# retainer.net
KiCad netlist of a schematic drawn in EAGLE
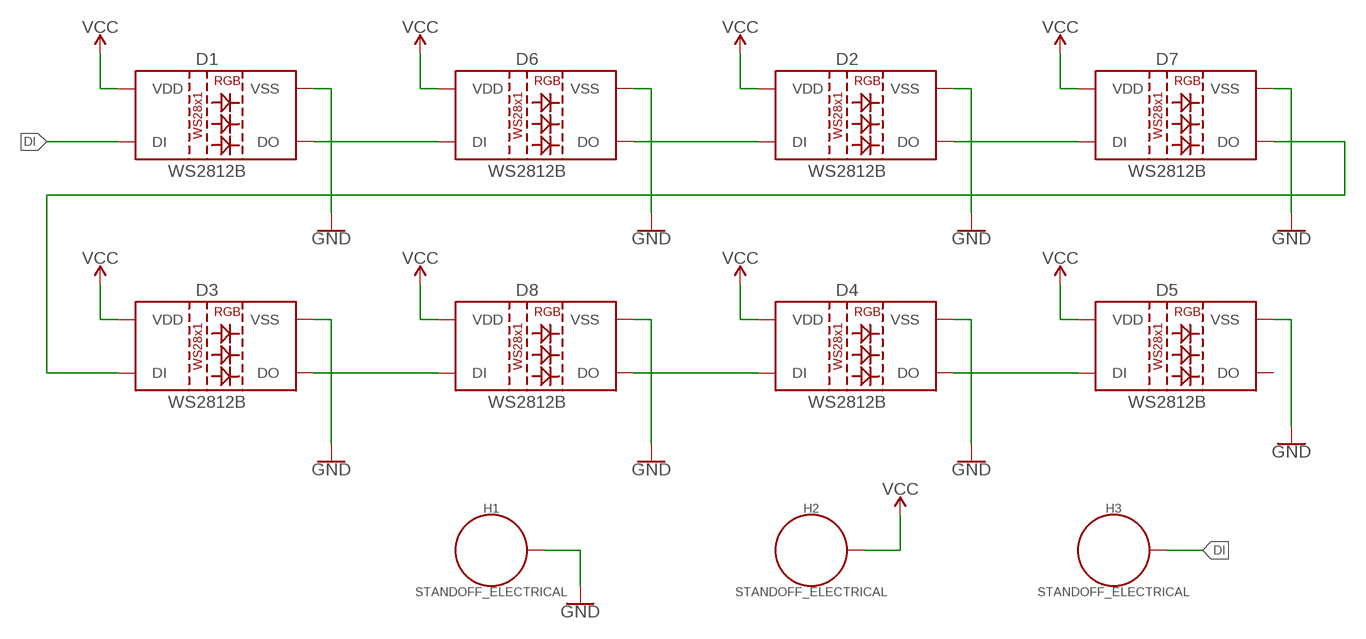
[diagram p0: schematic, sheet 1]

(export (version "E")
  (design (tool "Eeschema 10.0.6"))
  (components
    (comp (ref "D1")
      (value "WS2812B")
      (footprint "eagle-import:WS2812B")
      (libsource (lib "eagle-import") (part "WS2812B"))
    )
    (comp (ref "D2")
      (value "WS2812B")
      (footprint "eagle-import:WS2812B")
      (libsource (lib "eagle-import") (part "WS2812B"))
    )
    (comp (ref "D3")
      (value "WS2812B")
      (footprint "eagle-import:WS2812B")
      (libsource (lib "eagle-import") (part "WS2812B"))
    )
    (comp (ref "D4")
      (value "WS2812B")
      (footprint "eagle-import:WS2812B")
      (libsource (lib "eagle-import") (part "WS2812B"))
    )
    (comp (ref "D5")
      (value "WS2812B")
      (footprint "eagle-import:WS2812B")
      (libsource (lib "eagle-import") (part "WS2812B"))
    )
    (comp (ref "D6")
      (value "WS2812B")
      (footprint "eagle-import:WS2812B")
      (libsource (lib "eagle-import") (part "WS2812B"))
    )
    (comp (ref "D7")
      (value "WS2812B")
      (footprint "eagle-import:WS2812B")
      (libsource (lib "eagle-import") (part "WS2812B"))
    )
    (comp (ref "D8")
      (value "WS2812B")
      (footprint "eagle-import:WS2812B")
      (libsource (lib "eagle-import") (part "WS2812B"))
    )
    (comp (ref "H1")
      (value "STANDOFF_ELECTRICAL")
      (footprint "eagle-import:STANDOFF-ELECTRICAL")
      (libsource (lib "eagle-import") (part "STANDOFF_ELECTRICAL"))
    )
    (comp (ref "H2")
      (value "STANDOFF_ELECTRICAL")
      (footprint "eagle-import:STANDOFF-ELECTRICAL")
      (libsource (lib "eagle-import") (part "STANDOFF_ELECTRICAL"))
    )
    (comp (ref "H3")
      (value "STANDOFF_ELECTRICAL")
      (footprint "eagle-import:STANDOFF-ELECTRICAL")
      (libsource (lib "eagle-import") (part "STANDOFF_ELECTRICAL"))
    )
  )
  (nets
    (net (code "1") (name "DI") (class "Default")
      (node (ref "D1") (pin "4") (pinfunction "DI_4") (pintype "bidirectional"))
      (node (ref "H3") (pin "P1") (pinfunction "P$1_P1") (pintype "bidirectional"))
    )
    (net (code "2") (name "GND") (class "Default")
      (node (ref "D1") (pin "3") (pinfunction "VSS_3") (pintype "bidirectional"))
      (node (ref "D2") (pin "3") (pinfunction "VSS_3") (pintype "bidirectional"))
      (node (ref "D3") (pin "3") (pinfunction "VSS_3") (pintype "bidirectional"))
      (node (ref "D4") (pin "3") (pinfunction "VSS_3") (pintype "bidirectional"))
      (node (ref "D5") (pin "3") (pinfunction "VSS_3") (pintype "bidirectional"))
      (node (ref "D6") (pin "3") (pinfunction "VSS_3") (pintype "bidirectional"))
      (node (ref "D7") (pin "3") (pinfunction "VSS_3") (pintype "bidirectional"))
      (node (ref "D8") (pin "3") (pinfunction "VSS_3") (pintype "bidirectional"))
      (node (ref "H1") (pin "P1") (pinfunction "P$1_P1") (pintype "bidirectional"))
    )
    (net (code "3") (name "Net-(D1-DO)") (class "Default")
      (node (ref "D1") (pin "2") (pinfunction "DO_2") (pintype "bidirectional"))
      (node (ref "D6") (pin "4") (pinfunction "DI_4") (pintype "bidirectional"))
    )
    (net (code "4") (name "Net-(D2-DI)") (class "Default")
      (node (ref "D2") (pin "4") (pinfunction "DI_4") (pintype "bidirectional"))
      (node (ref "D6") (pin "2") (pinfunction "DO_2") (pintype "bidirectional"))
    )
    (net (code "5") (name "Net-(D2-DO)") (class "Default")
      (node (ref "D2") (pin "2") (pinfunction "DO_2") (pintype "bidirectional"))
      (node (ref "D7") (pin "4") (pinfunction "DI_4") (pintype "bidirectional"))
    )
    (net (code "6") (name "Net-(D3-DI)") (class "Default")
      (node (ref "D3") (pin "4") (pinfunction "DI_4") (pintype "bidirectional"))
      (node (ref "D7") (pin "2") (pinfunction "DO_2") (pintype "bidirectional"))
    )
    (net (code "7") (name "Net-(D3-DO)") (class "Default")
      (node (ref "D3") (pin "2") (pinfunction "DO_2") (pintype "bidirectional"))
      (node (ref "D8") (pin "4") (pinfunction "DI_4") (pintype "bidirectional"))
    )
    (net (code "8") (name "Net-(D4-DI)") (class "Default")
      (node (ref "D4") (pin "4") (pinfunction "DI_4") (pintype "bidirectional"))
      (node (ref "D8") (pin "2") (pinfunction "DO_2") (pintype "bidirectional"))
    )
    (net (code "9") (name "Net-(D4-DO)") (class "Default")
      (node (ref "D4") (pin "2") (pinfunction "DO_2") (pintype "bidirectional"))
      (node (ref "D5") (pin "4") (pinfunction "DI_4") (pintype "bidirectional"))
    )
    (net (code "10") (name "VCC") (class "Default")
      (node (ref "D1") (pin "1") (pinfunction "VDD_1") (pintype "bidirectional"))
      (node (ref "D2") (pin "1") (pinfunction "VDD_1") (pintype "bidirectional"))
      (node (ref "D3") (pin "1") (pinfunction "VDD_1") (pintype "bidirectional"))
      (node (ref "D4") (pin "1") (pinfunction "VDD_1") (pintype "bidirectional"))
      (node (ref "D5") (pin "1") (pinfunction "VDD_1") (pintype "bidirectional"))
      (node (ref "D6") (pin "1") (pinfunction "VDD_1") (pintype "bidirectional"))
      (node (ref "D7") (pin "1") (pinfunction "VDD_1") (pintype "bidirectional"))
      (node (ref "D8") (pin "1") (pinfunction "VDD_1") (pintype "bidirectional"))
      (node (ref "H2") (pin "P1") (pinfunction "P$1_P1") (pintype "bidirectional"))
    )
    (net (code "11") (name "unconnected-(D5-DO-Pad2)") (class "Default")
      (node (ref "D5") (pin "2") (pinfunction "DO_2") (pintype "bidirectional"))
    )
  )
)
